# Current_Driver_2.net
KiCad netlist of a schematic drawn in Altium Designer
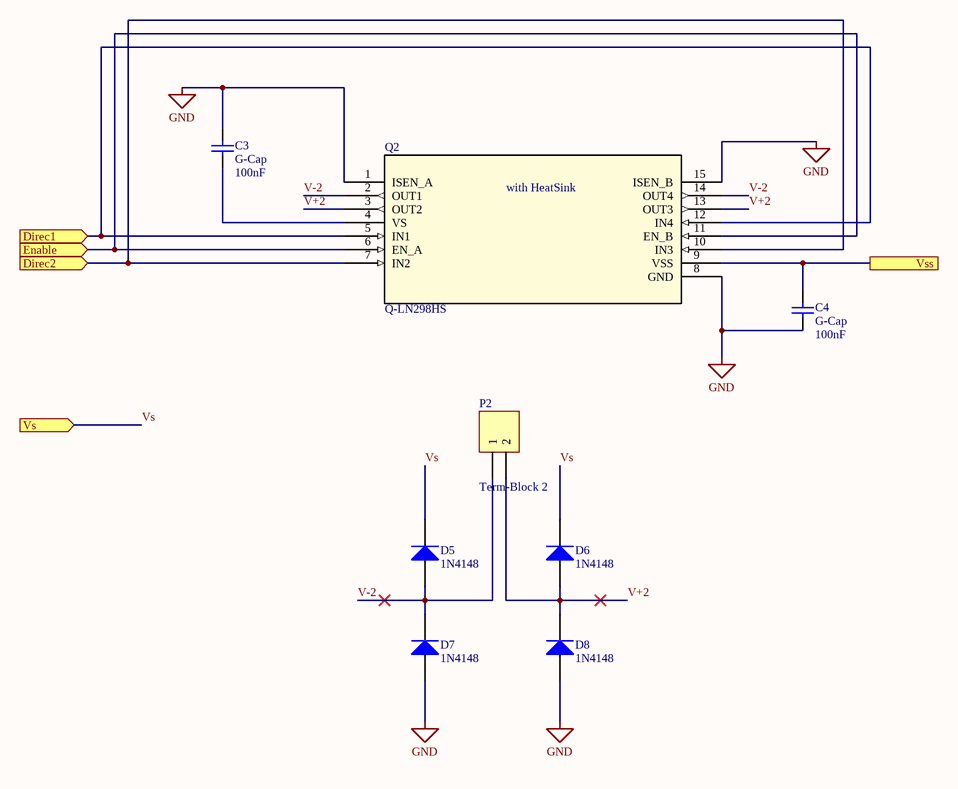
[diagram p0: Current_Driver_2.SchDoc]

(export (version "E")
  (design (tool "Eeschema 10.0.6"))
  (components
    (comp (ref "C3")
      (value "G-Cap")
      (footprint "Cap2.54mm_LGE1.0")
      (description "Capacitor (specify value)")
      (fields (field (name "ALTIUM_VALUE") "100nF") (field (name "PUBLISHER") "Altium Limited"))
      (libsource (lib "PartsDatabaseV16.1") (part "G-Cap"))
    )
    (comp (ref "C4")
      (value "G-Cap")
      (footprint "Cap2.54mm_LGE1.0")
      (description "Capacitor (specify value)")
      (fields (field (name "ALTIUM_VALUE") "100nF") (field (name "PUBLISHER") "Altium Limited"))
      (libsource (lib "PartsDatabaseV16.1") (part "G-Cap"))
    )
    (comp (ref "D5")
      (value "1N4148")
      (footprint "DO-41_XLGE1.2")
      (description "High-speed Diode")
      (libsource (lib "PartsDatabaseV16.1") (part "T-DiodeRect"))
    )
    (comp (ref "D6")
      (value "1N4148")
      (footprint "DO-41_XLGE1.2")
      (description "High-speed Diode")
      (libsource (lib "PartsDatabaseV16.1") (part "T-DiodeRect"))
    )
    (comp (ref "D7")
      (value "1N4148")
      (footprint "DO-41_XLGE1.2")
      (description "High-speed Diode")
      (libsource (lib "PartsDatabaseV16.1") (part "T-DiodeRect"))
    )
    (comp (ref "D8")
      (value "1N4148")
      (footprint "DO-41_XLGE1.2")
      (description "High-speed Diode")
      (libsource (lib "PartsDatabaseV16.1") (part "T-DiodeRect"))
    )
    (comp (ref "P2")
      (value "Term-Block 2")
      (footprint "TERM-BLOCK-5.08MM-2POS")
      (description "Terminal-Block 1x2")
      (fields (field (name "PUBLISHER") "Altium Limited"))
      (libsource (lib "PartsDatabaseV16.1") (part "C-Block2"))
    )
    (comp (ref "Q2")
      (value "Q-LN298HS")
      (footprint "Multiwatt15_V_ELEC391HS")
      (description "LN298 - IC Bridge Driver Par 15Multiwatt")
      (fields
        (field (name "MANUFACTURER_PART_NUMBER") "L298N")
        (field (name "COPYRIGHT") "Copyright (C) 2015 Accelerated Designs. All rights reserved")
      )
      (libsource (lib "Additional Parts 391") (part "Q-LN298HS"))
    )
  )
  (nets
    (net (code "1") (name "/Direc1") (class "Default")
      (node (ref "Q2") (pin "12") (pinfunction "IN4_12") (pintype "input"))
      (node (ref "Q2") (pin "5") (pinfunction "IN1_5") (pintype "input"))
    )
    (net (code "2") (name "/Direc2") (class "Default")
      (node (ref "Q2") (pin "10") (pinfunction "IN3_10") (pintype "input"))
      (node (ref "Q2") (pin "7") (pinfunction "IN2_7") (pintype "input"))
    )
    (net (code "3") (name "/Enable") (class "Default")
      (node (ref "Q2") (pin "11") (pinfunction "EN_B_11") (pintype "input"))
      (node (ref "Q2") (pin "6") (pinfunction "EN_A_6") (pintype "input"))
    )
    (net (code "4") (name "/V+2") (class "Default")
      (node (ref "D6") (pin "1") (pinfunction "A_1") (pintype "passive"))
      (node (ref "D8") (pin "2") (pinfunction "K_2") (pintype "passive"))
      (node (ref "P2") (pin "2") (pinfunction "2_2") (pintype "passive"))
      (node (ref "Q2") (pin "13") (pinfunction "OUT3_13") (pintype "output"))
      (node (ref "Q2") (pin "3") (pinfunction "OUT2_3") (pintype "output"))
    )
    (net (code "5") (name "/V-2") (class "Default")
      (node (ref "D5") (pin "1") (pinfunction "A_1") (pintype "passive"))
      (node (ref "D7") (pin "2") (pinfunction "K_2") (pintype "passive"))
      (node (ref "P2") (pin "1") (pinfunction "1_1") (pintype "passive"))
      (node (ref "Q2") (pin "14") (pinfunction "OUT4_14") (pintype "output"))
      (node (ref "Q2") (pin "2") (pinfunction "OUT1_2") (pintype "output"))
    )
    (net (code "6") (name "/Vs") (class "Default")
      (node (ref "D5") (pin "2") (pinfunction "K_2") (pintype "passive"))
      (node (ref "D6") (pin "2") (pinfunction "K_2") (pintype "passive"))
    )
    (net (code "7") (name "/Vss") (class "Default")
      (node (ref "C4") (pin "2") (pinfunction "2_2") (pintype "passive"))
      (node (ref "Q2") (pin "9") (pinfunction "VSS_9") (pintype "power_in"))
    )
    (net (code "8") (name "GND") (class "Default")
      (node (ref "C3") (pin "2") (pinfunction "2_2") (pintype "passive"))
      (node (ref "C4") (pin "1") (pinfunction "1_1") (pintype "passive"))
      (node (ref "D7") (pin "1") (pinfunction "A_1") (pintype "passive"))
      (node (ref "D8") (pin "1") (pinfunction "A_1") (pintype "passive"))
      (node (ref "Q2") (pin "1") (pinfunction "ISEN_A_1") (pintype "passive"))
      (node (ref "Q2") (pin "15") (pinfunction "ISEN_B_15") (pintype "passive"))
      (node (ref "Q2") (pin "8") (pinfunction "GND_8") (pintype "power_in"))
    )
    (net (code "9") (name "Net-(Q2-VS)") (class "Default")
      (node (ref "C3") (pin "1") (pinfunction "1_1") (pintype "passive"))
      (node (ref "Q2") (pin "4") (pinfunction "VS_4") (pintype "power_in"))
    )
  )
)
